# Frame2TTL_v3_1.net
KiCad netlist of a schematic drawn in EAGLE
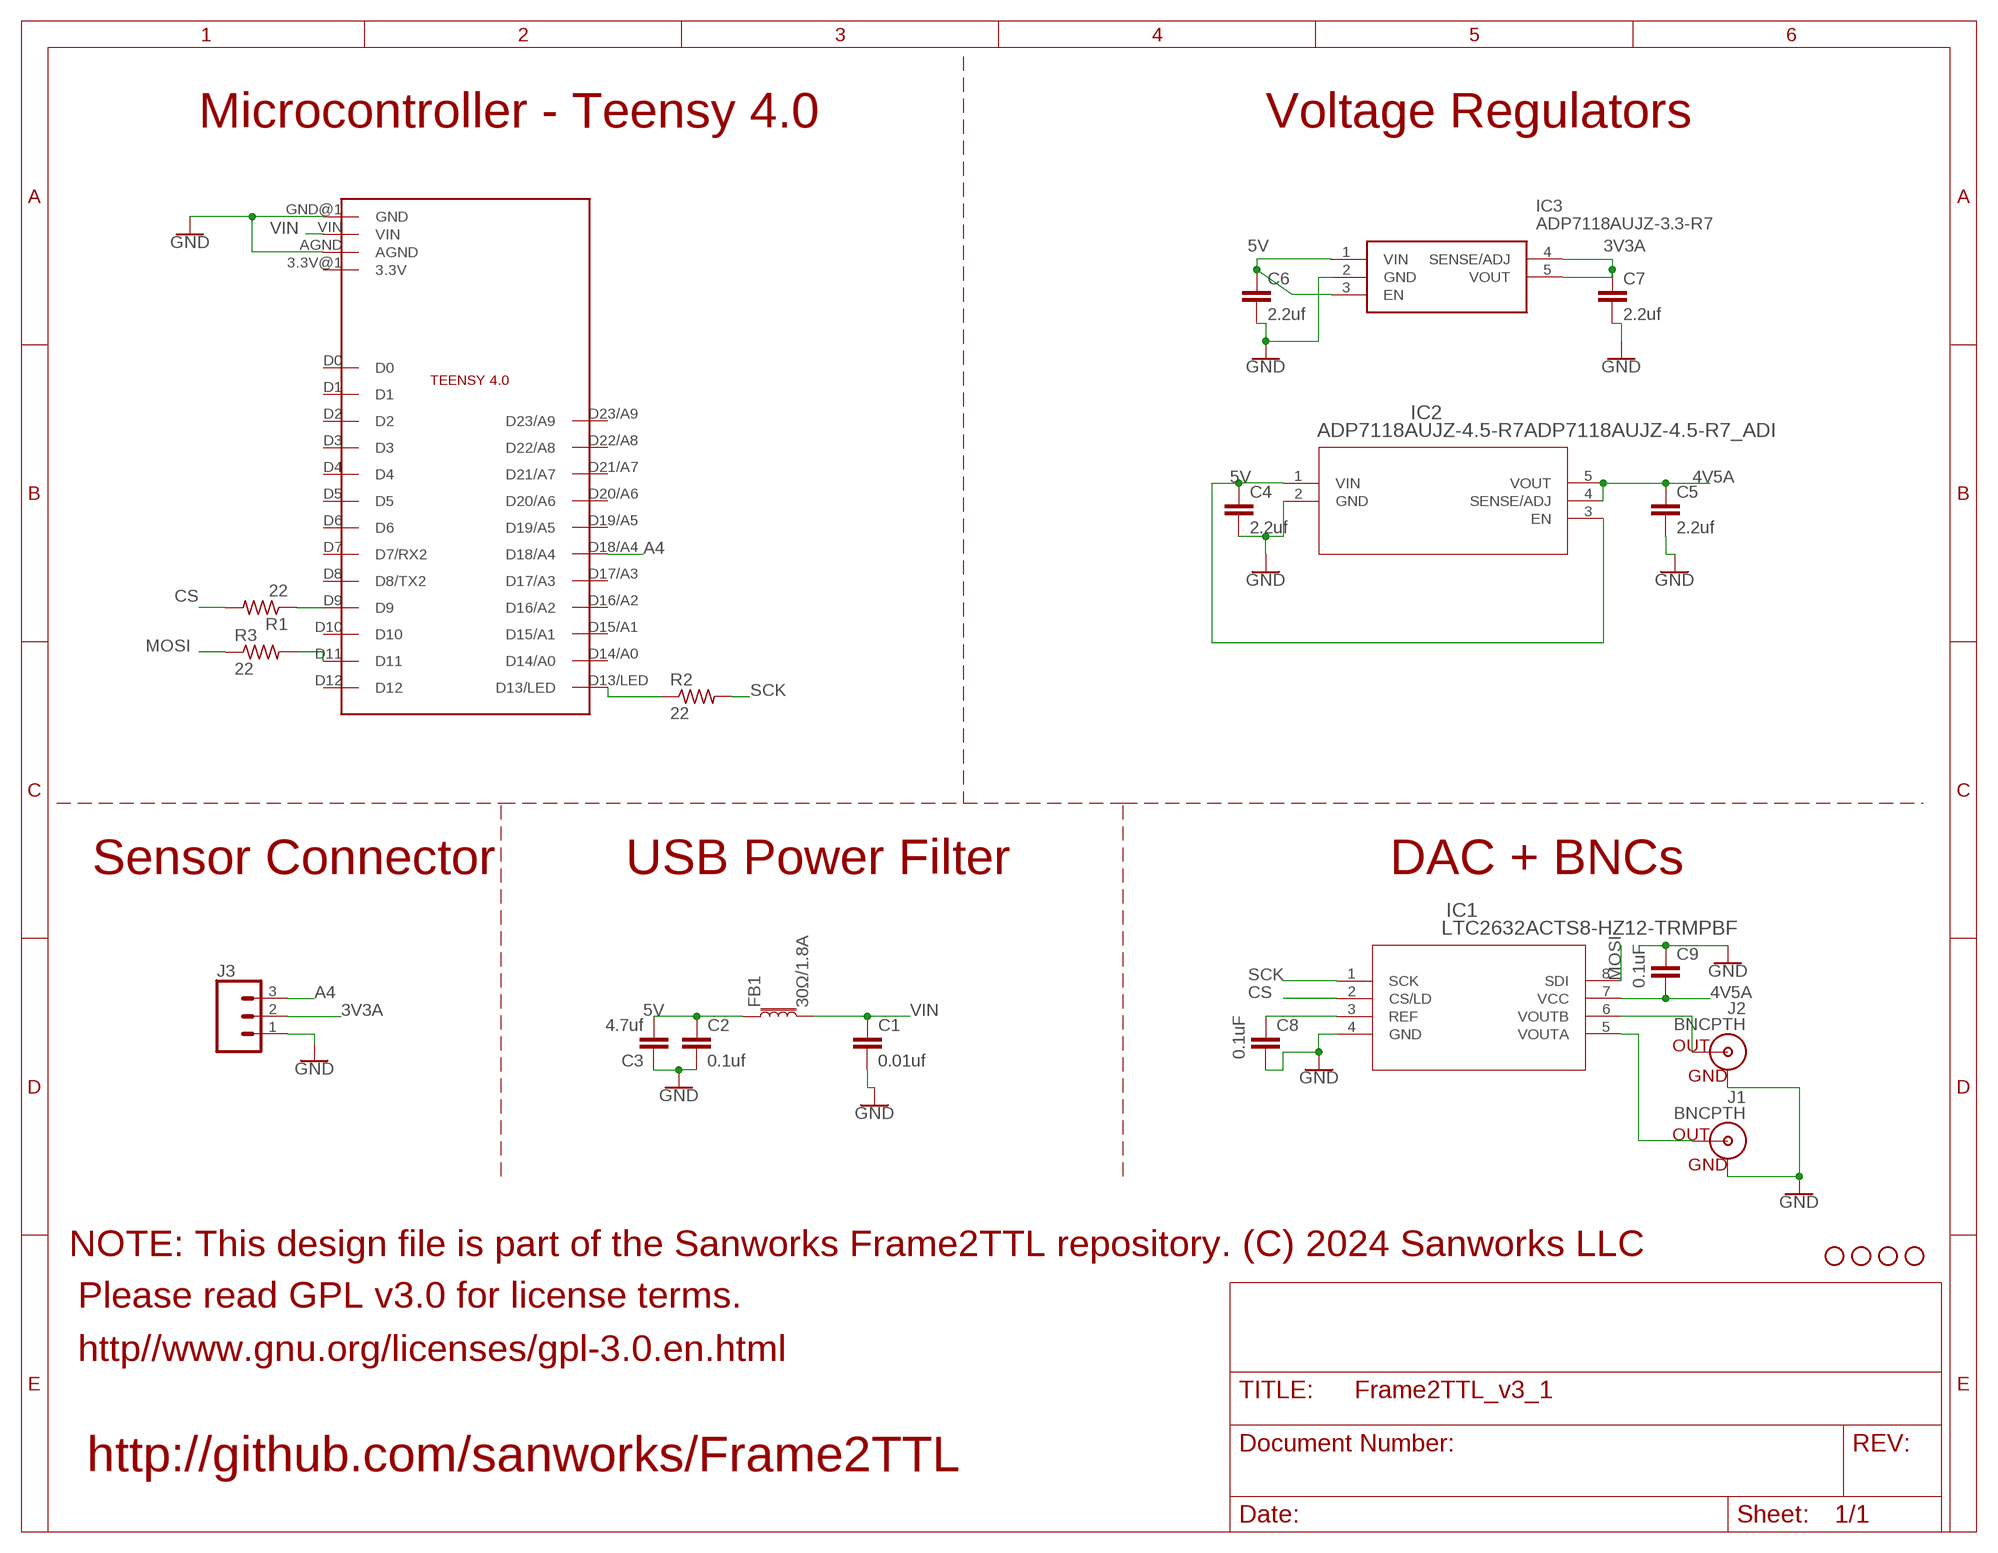
[diagram p0: schematic, sheet 1]

(export (version "E")
  (design (tool "Eeschema 10.0.6"))
  (components
    (comp (ref "C1")
      (value "0.01uf")
      (footprint "eagle-import:0805")
      (libsource (lib "eagle-import") (part "10UF-0805-10V-10%"))
    )
    (comp (ref "C2")
      (value "0.1uf")
      (footprint "eagle-import:0805")
      (libsource (lib "eagle-import") (part "10UF-0805-10V-10%"))
    )
    (comp (ref "C3")
      (value "4.7uf")
      (footprint "eagle-import:1206@2")
      (libsource (lib "eagle-import") (part "CAP1206"))
    )
    (comp (ref "C4")
      (value "2.2uf")
      (footprint "eagle-import:0805")
      (libsource (lib "eagle-import") (part "1.0UF-0805-25V-10%"))
    )
    (comp (ref "C5")
      (value "2.2uf")
      (footprint "eagle-import:0805")
      (libsource (lib "eagle-import") (part "1.0UF-0805-25V-10%"))
    )
    (comp (ref "C6")
      (value "2.2uf")
      (footprint "eagle-import:0805")
      (libsource (lib "eagle-import") (part "1.0UF-0805-25V-10%"))
    )
    (comp (ref "C7")
      (value "2.2uf")
      (footprint "eagle-import:0805")
      (libsource (lib "eagle-import") (part "1.0UF-0805-25V-10%"))
    )
    (comp (ref "C8")
      (value "0.1uF")
      (footprint "eagle-import:0805")
      (libsource (lib "eagle-import") (part "1.0UF-0805-25V-10%"))
    )
    (comp (ref "C9")
      (value "0.1uF")
      (footprint "eagle-import:0805")
      (libsource (lib "eagle-import") (part "1.0UF-0805-25V-10%"))
    )
    (comp (ref "FB1")
      (value "30Ω/1.8A")
      (footprint "eagle-import:0603")
      (libsource (lib "eagle-import") (part "FERRITE_BEAD-0603"))
    )
    (comp (ref "H1")
      (value "STAND-OFF")
      (footprint "eagle-import:STAND-OFF")
      (libsource (lib "eagle-import") (part "STAND-OFF"))
    )
    (comp (ref "H2")
      (value "STAND-OFF")
      (footprint "eagle-import:STAND-OFF")
      (libsource (lib "eagle-import") (part "STAND-OFF"))
    )
    (comp (ref "H3")
      (value "STAND-OFF")
      (footprint "eagle-import:STAND-OFF")
      (libsource (lib "eagle-import") (part "STAND-OFF"))
    )
    (comp (ref "H4")
      (value "STAND-OFF")
      (footprint "eagle-import:STAND-OFF")
      (libsource (lib "eagle-import") (part "STAND-OFF"))
    )
    (comp (ref "IC1")
      (value "LTC2632ACTS8-HZ12-TRMPBF")
      (footprint "eagle-import:TSOT-23-8_1P625X2P9_ADI")
      (fields
        (field (name "MANUFACTURER_PART_NUMBER") "LTC2632AHTS8-LI12#TRMPBF")
        (field (name "COPYRIGHT") "Copyright (C) 2022 Ultra Librarian. All rights reserved.")
      )
      (libsource (lib "eagle-import") (part "LTC2632AHTS8-LI12TRMPBF"))
    )
    (comp (ref "IC2")
      (value "ADP7118AUJZ-4.5-R7ADP7118AUJZ-4.5-R7_ADI")
      (footprint "eagle-import:ADP7118AUJZ-4.5-R7_ADI")
      (fields
        (field (name "MANUFACTURER_PART_NUMBER") "ADP7118AUJZ-4.5-R7")
        (field (name "COPYRIGHT") "Copyright (C) 2023 Ultra Librarian. All rights reserved.")
      )
      (libsource (lib "eagle-import") (part "ADP7118AUJZ-4.5-R7ADP7118AUJZ-4.5-R7_ADI"))
    )
    (comp (ref "IC3")
      (value "ADP7118AUJZ-3.3-R7")
      (footprint "eagle-import:SOT95P280X100-5N")
      (fields (field (name "MOUSER_PART_NUMBER") "584-ADP7118AUJZ3.3R7"))
      (libsource (lib "eagle-import") (part "ADP7118AUJZ-3.3-R7"))
    )
    (comp (ref "J1")
      (value "BNCPTH")
      (footprint "eagle-import:BNC")
      (libsource (lib "eagle-import") (part "BNCPTH"))
    )
    (comp (ref "J2")
      (value "BNCPTH")
      (footprint "eagle-import:BNC")
      (libsource (lib "eagle-import") (part "BNCPTH"))
    )
    (comp (ref "J3")
      (value "CONN_03LOCK")
      (footprint "eagle-import:1X03_LOCK")
      (libsource (lib "eagle-import") (part "CONN_03LOCK"))
    )
    (comp (ref "MC1")
      (value "TEENSY4.0_SIMPLE_NO_VUSB")
      (footprint "eagle-import:TEENSY4.0_SIMPLE_NO_VUSB")
      (libsource (lib "eagle-import") (part "TEENSY4.0_SIMPLE_NO_VUSB"))
    )
    (comp (ref "R1")
      (value "22")
      (footprint "eagle-import:R0805")
      (libsource (lib "eagle-import") (part "R-US_R0805"))
    )
    (comp (ref "R2")
      (value "22")
      (footprint "eagle-import:R0805")
      (libsource (lib "eagle-import") (part "R-US_R0805"))
    )
    (comp (ref "R3")
      (value "22")
      (footprint "eagle-import:R0805")
      (libsource (lib "eagle-import") (part "R-US_R0805"))
    )
  )
  (nets
    (net (code "1") (name "/3V3A") (class "Default")
      (node (ref "C7") (pin "1") (pinfunction "1_1") (pintype "passive"))
      (node (ref "IC3") (pin "4") (pinfunction "SENSE/ADJ_4") (pintype "bidirectional"))
      (node (ref "IC3") (pin "5") (pinfunction "VOUT_5") (pintype "bidirectional"))
      (node (ref "J3") (pin "2") (pinfunction "2_2") (pintype "passive"))
    )
    (net (code "2") (name "/4V5A") (class "Default")
      (node (ref "C5") (pin "1") (pinfunction "1_1") (pintype "passive"))
      (node (ref "C9") (pin "2") (pinfunction "2_2") (pintype "passive"))
      (node (ref "IC1") (pin "7") (pinfunction "VCC_7") (pintype "power_in"))
      (node (ref "IC2") (pin "4") (pinfunction "SENSE/ADJ_4") (pintype "input"))
      (node (ref "IC2") (pin "5") (pinfunction "VOUT_5") (pintype "passive"))
    )
    (net (code "3") (name "/5V") (class "Default")
      (node (ref "C2") (pin "1") (pinfunction "1_1") (pintype "passive"))
      (node (ref "C3") (pin "2") (pinfunction "2_2") (pintype "passive"))
      (node (ref "C4") (pin "1") (pinfunction "1_1") (pintype "passive"))
      (node (ref "C6") (pin "1") (pinfunction "1_1") (pintype "passive"))
      (node (ref "FB1") (pin "1") (pinfunction "1_1") (pintype "passive"))
      (node (ref "IC2") (pin "1") (pinfunction "VIN_1") (pintype "power_in"))
      (node (ref "IC2") (pin "3") (pinfunction "EN_3") (pintype "input"))
      (node (ref "IC3") (pin "1") (pinfunction "VIN_1") (pintype "bidirectional"))
      (node (ref "IC3") (pin "3") (pinfunction "EN_3") (pintype "bidirectional"))
    )
    (net (code "4") (name "/A4") (class "Default")
      (node (ref "J3") (pin "3") (pinfunction "3_3") (pintype "passive"))
      (node (ref "MC1") (pin "D18/A4") (pinfunction "D18/A4_D18/A4") (pintype "bidirectional"))
    )
    (net (code "5") (name "/CS") (class "Default")
      (node (ref "IC1") (pin "2") (pinfunction "CS/LD_2") (pintype "passive"))
      (node (ref "R1") (pin "2") (pinfunction "2_2") (pintype "passive"))
    )
    (net (code "6") (name "/MOSI") (class "Default")
      (node (ref "IC1") (pin "8") (pinfunction "SDI_8") (pintype "passive"))
      (node (ref "R3") (pin "1") (pinfunction "1_1") (pintype "passive"))
    )
    (net (code "7") (name "/SCK") (class "Default")
      (node (ref "IC1") (pin "1") (pinfunction "SCK_1") (pintype "passive"))
      (node (ref "R2") (pin "2") (pinfunction "2_2") (pintype "passive"))
    )
    (net (code "8") (name "/VIN") (class "Default")
      (node (ref "C1") (pin "1") (pinfunction "1_1") (pintype "passive"))
      (node (ref "FB1") (pin "2") (pinfunction "2_2") (pintype "passive"))
      (node (ref "MC1") (pin "VIN") (pinfunction "VIN_VIN") (pintype "bidirectional"))
    )
    (net (code "9") (name "GND") (class "Default")
      (node (ref "C1") (pin "2") (pinfunction "2_2") (pintype "passive"))
      (node (ref "C2") (pin "2") (pinfunction "2_2") (pintype "passive"))
      (node (ref "C3") (pin "1") (pinfunction "1_1") (pintype "passive"))
      (node (ref "C4") (pin "2") (pinfunction "2_2") (pintype "passive"))
      (node (ref "C5") (pin "2") (pinfunction "2_2") (pintype "passive"))
      (node (ref "C6") (pin "2") (pinfunction "2_2") (pintype "passive"))
      (node (ref "C7") (pin "2") (pinfunction "2_2") (pintype "passive"))
      (node (ref "C8") (pin "2") (pinfunction "2_2") (pintype "passive"))
      (node (ref "C9") (pin "1") (pinfunction "1_1") (pintype "passive"))
      (node (ref "IC1") (pin "4") (pinfunction "GND_4") (pintype "passive"))
      (node (ref "IC2") (pin "2") (pinfunction "GND_2") (pintype "passive"))
      (node (ref "IC3") (pin "2") (pinfunction "GND_2") (pintype "bidirectional"))
      (node (ref "J1") (pin "GND") (pinfunction "GND_GND") (pintype "bidirectional"))
      (node (ref "J2") (pin "GND") (pinfunction "GND_GND") (pintype "bidirectional"))
      (node (ref "J3") (pin "1") (pinfunction "1_1") (pintype "passive"))
      (node (ref "MC1") (pin "AGND") (pinfunction "AGND_AGND") (pintype "bidirectional"))
      (node (ref "MC1") (pin "GND@1") (pinfunction "GND_GND@1") (pintype "bidirectional"))
    )
    (net (code "10") (name "Net-(IC1-REF)") (class "Default")
      (node (ref "C8") (pin "1") (pinfunction "1_1") (pintype "passive"))
      (node (ref "IC1") (pin "3") (pinfunction "REF_3") (pintype "passive"))
    )
    (net (code "11") (name "Net-(IC1-VOUTA)") (class "Default")
      (node (ref "IC1") (pin "5") (pinfunction "VOUTA_5") (pintype "output"))
      (node (ref "J1") (pin "S") (pinfunction "OUT_S") (pintype "bidirectional"))
    )
    (net (code "12") (name "Net-(IC1-VOUTB)") (class "Default")
      (node (ref "IC1") (pin "6") (pinfunction "VOUTB_6") (pintype "output"))
      (node (ref "J2") (pin "S") (pinfunction "OUT_S") (pintype "bidirectional"))
    )
    (net (code "13") (name "Net-(MC1-PadD9)") (class "Default")
      (node (ref "MC1") (pin "D9") (pinfunction "D9_D9") (pintype "bidirectional"))
      (node (ref "R1") (pin "1") (pinfunction "1_1") (pintype "passive"))
    )
    (net (code "14") (name "Net-(MC1-PadD11)") (class "Default")
      (node (ref "MC1") (pin "D11") (pinfunction "D11_D11") (pintype "bidirectional"))
      (node (ref "R3") (pin "2") (pinfunction "2_2") (pintype "passive"))
    )
    (net (code "15") (name "Net-(MC1-PadD13{slash}LED)") (class "Default")
      (node (ref "MC1") (pin "D13/LED") (pinfunction "D13/LED_D13/LED") (pintype "bidirectional"))
      (node (ref "R2") (pin "1") (pinfunction "1_1") (pintype "passive"))
    )
    (net (code "16") (name "unconnected-(MC1-3.3V-Pad3.3V@1)") (class "Default")
      (node (ref "MC1") (pin "3.3V@1") (pinfunction "3.3V_3.3V@1") (pintype "bidirectional"))
    )
    (net (code "17") (name "unconnected-(MC1-D7{slash}RX2-PadD7)") (class "Default")
      (node (ref "MC1") (pin "D7") (pinfunction "D7/RX2_D7") (pintype "bidirectional"))
    )
    (net (code "18") (name "unconnected-(MC1-D8{slash}TX2-PadD8)") (class "Default")
      (node (ref "MC1") (pin "D8") (pinfunction "D8/TX2_D8") (pintype "bidirectional"))
    )
    (net (code "19") (name "unconnected-(MC1-PadD0)") (class "Default")
      (node (ref "MC1") (pin "D0") (pinfunction "D0_D0") (pintype "bidirectional"))
    )
    (net (code "20") (name "unconnected-(MC1-PadD1)") (class "Default")
      (node (ref "MC1") (pin "D1") (pinfunction "D1_D1") (pintype "bidirectional"))
    )
    (net (code "21") (name "unconnected-(MC1-PadD2)") (class "Default")
      (node (ref "MC1") (pin "D2") (pinfunction "D2_D2") (pintype "bidirectional"))
    )
    (net (code "22") (name "unconnected-(MC1-PadD3)") (class "Default")
      (node (ref "MC1") (pin "D3") (pinfunction "D3_D3") (pintype "bidirectional"))
    )
    (net (code "23") (name "unconnected-(MC1-PadD4)") (class "Default")
      (node (ref "MC1") (pin "D4") (pinfunction "D4_D4") (pintype "bidirectional"))
    )
    (net (code "24") (name "unconnected-(MC1-PadD5)") (class "Default")
      (node (ref "MC1") (pin "D5") (pinfunction "D5_D5") (pintype "bidirectional"))
    )
    (net (code "25") (name "unconnected-(MC1-PadD6)") (class "Default")
      (node (ref "MC1") (pin "D6") (pinfunction "D6_D6") (pintype "bidirectional"))
    )
    (net (code "26") (name "unconnected-(MC1-PadD10)") (class "Default")
      (node (ref "MC1") (pin "D10") (pinfunction "D10_D10") (pintype "bidirectional"))
    )
    (net (code "27") (name "unconnected-(MC1-PadD12)") (class "Default")
      (node (ref "MC1") (pin "D12") (pinfunction "D12_D12") (pintype "bidirectional"))
    )
    (net (code "28") (name "unconnected-(MC1-PadD14{slash}A0)") (class "Default")
      (node (ref "MC1") (pin "D14/A0") (pinfunction "D14/A0_D14/A0") (pintype "bidirectional"))
    )
    (net (code "29") (name "unconnected-(MC1-PadD15{slash}A1)") (class "Default")
      (node (ref "MC1") (pin "D15/A1") (pinfunction "D15/A1_D15/A1") (pintype "bidirectional"))
    )
    (net (code "30") (name "unconnected-(MC1-PadD16{slash}A2)") (class "Default")
      (node (ref "MC1") (pin "D16/A2") (pinfunction "D16/A2_D16/A2") (pintype "bidirectional"))
    )
    (net (code "31") (name "unconnected-(MC1-PadD17{slash}A3)") (class "Default")
      (node (ref "MC1") (pin "D17/A3") (pinfunction "D17/A3_D17/A3") (pintype "bidirectional"))
    )
    (net (code "32") (name "unconnected-(MC1-PadD19{slash}A5)") (class "Default")
      (node (ref "MC1") (pin "D19/A5") (pinfunction "D19/A5_D19/A5") (pintype "bidirectional"))
    )
    (net (code "33") (name "unconnected-(MC1-PadD20{slash}A6)") (class "Default")
      (node (ref "MC1") (pin "D20/A6") (pinfunction "D20/A6_D20/A6") (pintype "bidirectional"))
    )
    (net (code "34") (name "unconnected-(MC1-PadD21{slash}A7)") (class "Default")
      (node (ref "MC1") (pin "D21/A7") (pinfunction "D21/A7_D21/A7") (pintype "bidirectional"))
    )
    (net (code "35") (name "unconnected-(MC1-PadD22{slash}A8)") (class "Default")
      (node (ref "MC1") (pin "D22/A8") (pinfunction "D22/A8_D22/A8") (pintype "bidirectional"))
    )
    (net (code "36") (name "unconnected-(MC1-PadD23{slash}A9)") (class "Default")
      (node (ref "MC1") (pin "D23/A9") (pinfunction "D23/A9_D23/A9") (pintype "bidirectional"))
    )
  )
)
